# BeagleQ-v03.net
KiCad netlist of a schematic drawn in EAGLE
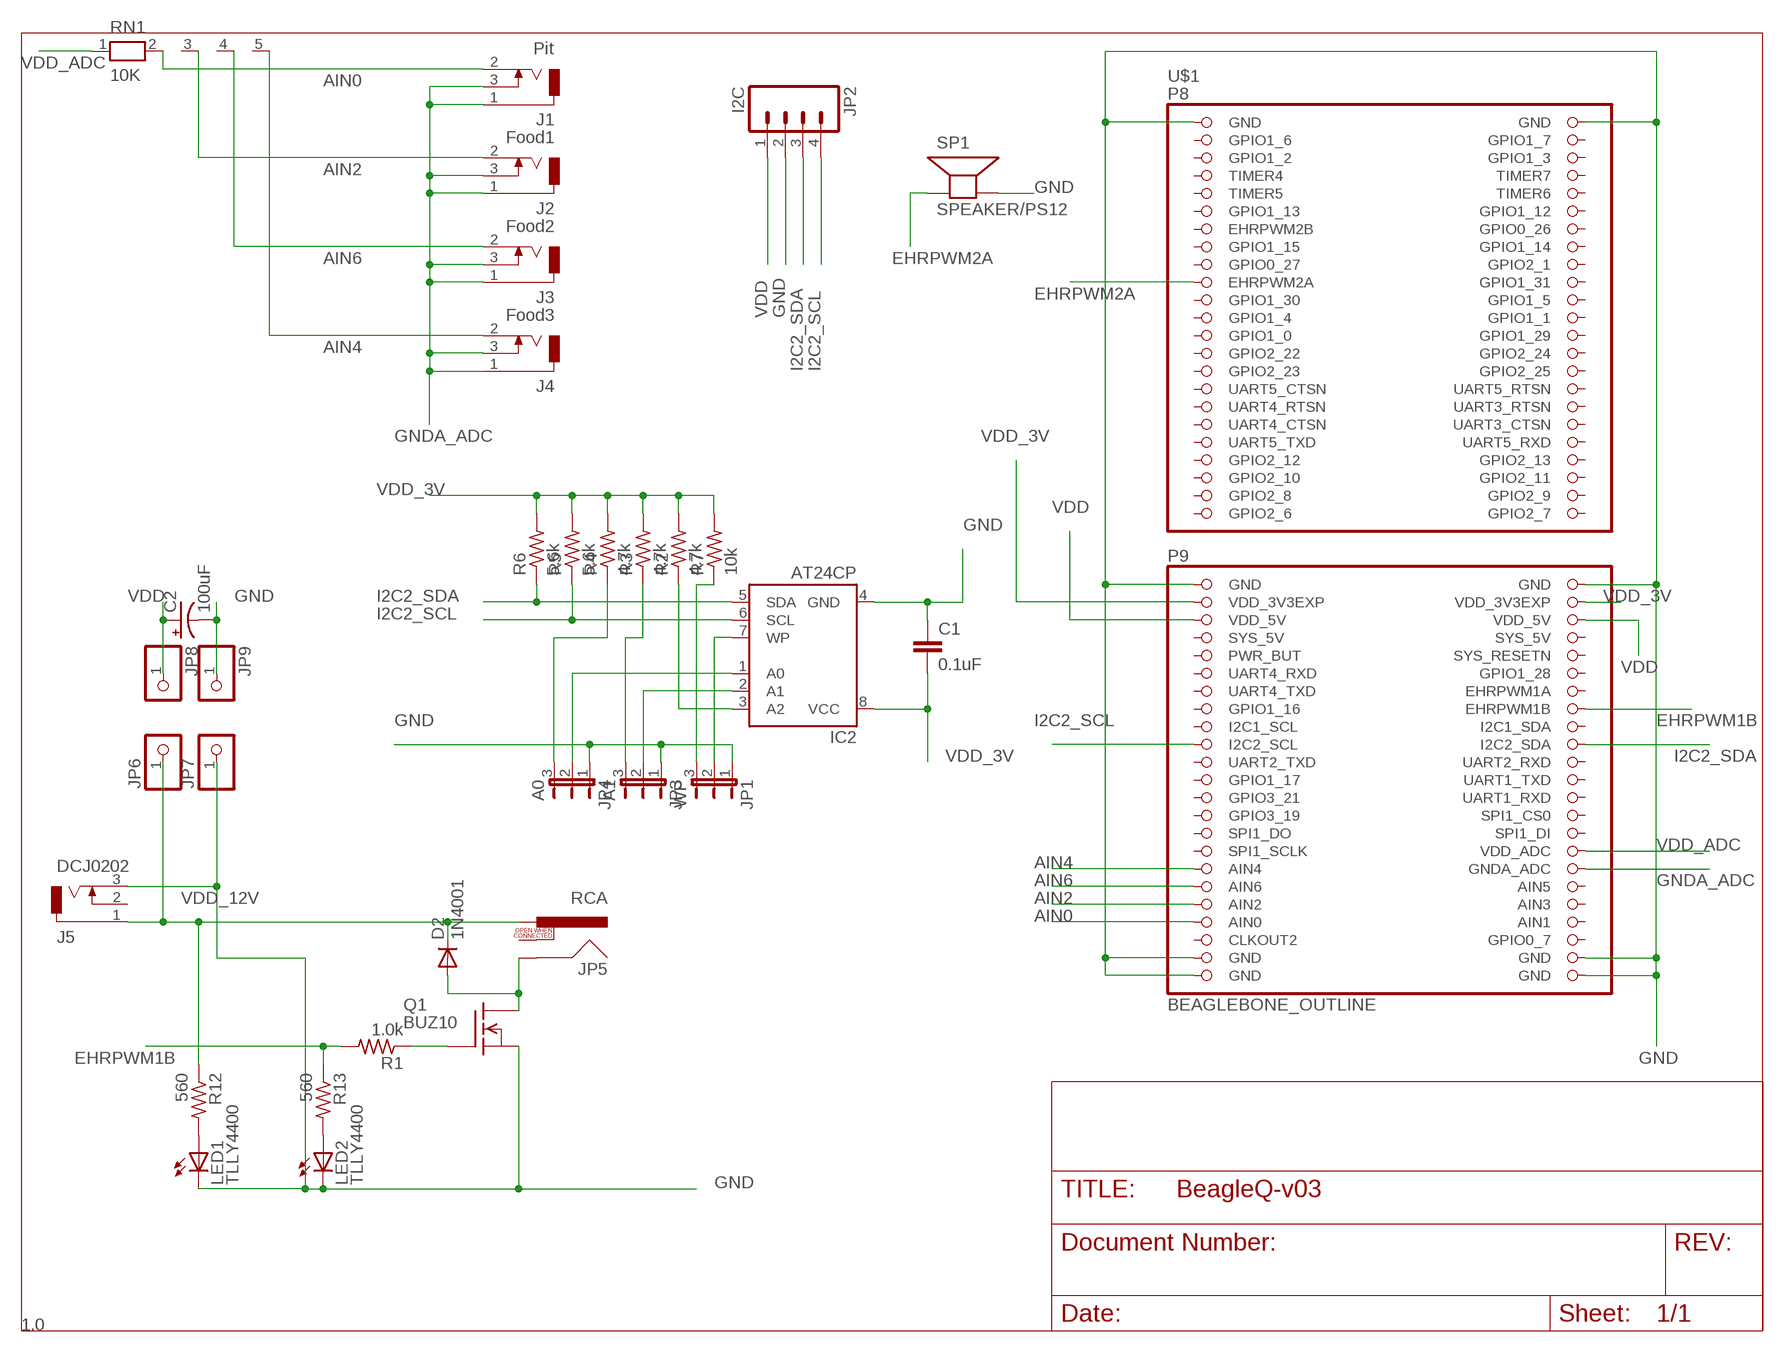
[diagram p0: schematic, sheet 1]

(export (version "E")
  (design (tool "Eeschema 10.0.6"))
  (components
    (comp (ref "C1")
      (value "0.1uF")
      (footprint "eagle-import:C2.5-2")
      (libsource (lib "eagle-import") (part "C2.5/2"))
    )
    (comp (ref "C2")
      (value "100uF")
      (footprint "eagle-import:E2,5-6E")
      (libsource (lib "eagle-import") (part "CPOL-USE2,5-6E"))
    )
    (comp (ref "D2")
      (value "1N4001")
      (footprint "eagle-import:DO41-10")
      (libsource (lib "eagle-import") (part "1N4004"))
    )
    (comp (ref "IC2")
      (value "AT24CP")
      (footprint "eagle-import:DIL08")
      (fields (field (name "MPN") "AT24C1024BW-SH-B"))
      (libsource (lib "eagle-import") (part "AT24CP"))
    )
    (comp (ref "J1")
      (value "Pit")
      (footprint "eagle-import:DCJ0202")
      (libsource (lib "eagle-import") (part "houseofbeck_DCJ0202"))
    )
    (comp (ref "J2")
      (value "Food1")
      (footprint "eagle-import:DCJ0202")
      (libsource (lib "eagle-import") (part "houseofbeck_DCJ0202"))
    )
    (comp (ref "J3")
      (value "Food2")
      (footprint "eagle-import:DCJ0202")
      (libsource (lib "eagle-import") (part "houseofbeck_DCJ0202"))
    )
    (comp (ref "J4")
      (value "Food3")
      (footprint "eagle-import:DCJ0202")
      (libsource (lib "eagle-import") (part "houseofbeck_DCJ0202"))
    )
    (comp (ref "J5")
      (value "DCJ0202")
      (footprint "eagle-import:DCJ0202")
      (libsource (lib "eagle-import") (part "DCJ0202"))
    )
    (comp (ref "JP1")
      (value "WP")
      (footprint "eagle-import:JP2")
      (libsource (lib "eagle-import") (part "JP2E"))
    )
    (comp (ref "JP2")
      (value "I2C")
      (footprint "eagle-import:1X04")
      (libsource (lib "eagle-import") (part "M04PTH"))
    )
    (comp (ref "JP3")
      (value "A1")
      (footprint "eagle-import:JP2")
      (libsource (lib "eagle-import") (part "JP2E"))
    )
    (comp (ref "JP4")
      (value "A0")
      (footprint "eagle-import:JP2")
      (libsource (lib "eagle-import") (part "JP2E"))
    )
    (comp (ref "JP5")
      (value "RCA")
      (footprint "eagle-import:RCA")
      (libsource (lib "eagle-import") (part "RCA"))
    )
    (comp (ref "JP6")
      (value "PINHD-1X1")
      (footprint "eagle-import:1X01")
      (libsource (lib "eagle-import") (part "PINHD-1X1"))
    )
    (comp (ref "JP7")
      (value "PINHD-1X1")
      (footprint "eagle-import:1X01")
      (libsource (lib "eagle-import") (part "PINHD-1X1"))
    )
    (comp (ref "JP8")
      (value "PINHD-1X1")
      (footprint "eagle-import:1X01")
      (libsource (lib "eagle-import") (part "PINHD-1X1"))
    )
    (comp (ref "JP9")
      (value "PINHD-1X1")
      (footprint "eagle-import:1X01")
      (libsource (lib "eagle-import") (part "PINHD-1X1"))
    )
    (comp (ref "LED1")
      (value "TLLY4400")
      (footprint "eagle-import:LED3MM")
      (fields (field (name "MF") "VISHAY SEMICONDUCTOR"))
      (libsource (lib "eagle-import") (part "TLLY4400"))
    )
    (comp (ref "LED2")
      (value "TLLY4400")
      (footprint "eagle-import:LED3MM")
      (fields (field (name "MF") "VISHAY SEMICONDUCTOR"))
      (libsource (lib "eagle-import") (part "TLLY4400"))
    )
    (comp (ref "Q1")
      (value "BUZ10")
      (footprint "eagle-import:TO220")
      (libsource (lib "eagle-import") (part "BUZ10"))
    )
    (comp (ref "R1")
      (value "1.0k")
      (footprint "eagle-import:0207_10")
      (libsource (lib "eagle-import") (part "R-US_0207/10"))
    )
    (comp (ref "R2")
      (value "4.7k")
      (footprint "eagle-import:0207_10")
      (libsource (lib "eagle-import") (part "R-US_0207/10"))
    )
    (comp (ref "R3")
      (value "4.7k")
      (footprint "eagle-import:0207_10")
      (libsource (lib "eagle-import") (part "R-US_0207/10"))
    )
    (comp (ref "R4")
      (value "4.7k")
      (footprint "eagle-import:0207_10")
      (libsource (lib "eagle-import") (part "R-US_0207/10"))
    )
    (comp (ref "R5")
      (value "5.6k")
      (footprint "eagle-import:0207_10")
      (libsource (lib "eagle-import") (part "R-US_0207/10"))
    )
    (comp (ref "R6")
      (value "5.6k")
      (footprint "eagle-import:0207_10")
      (libsource (lib "eagle-import") (part "R-US_0207/10"))
    )
    (comp (ref "R7")
      (value "10k")
      (footprint "eagle-import:0207_10")
      (libsource (lib "eagle-import") (part "R-US_0207/10"))
    )
    (comp (ref "R12")
      (value "560")
      (footprint "eagle-import:0207_10")
      (libsource (lib "eagle-import") (part "R-US_0207/10"))
    )
    (comp (ref "R13")
      (value "560")
      (footprint "eagle-import:0207_10")
      (libsource (lib "eagle-import") (part "R-US_0207/10"))
    )
    (comp (ref "RN1")
      (value "10K")
      (footprint "eagle-import:RN-5")
      (libsource (lib "eagle-import") (part "RN04"))
    )
    (comp (ref "SP1")
      (value "SPEAKER/PS12")
      (footprint "eagle-import:PS12")
      (libsource (lib "eagle-import") (part "SPEAKER/PS12"))
    )
    (comp (ref "U$1")
      (value "BEAGLEBONE_OUTLINE")
      (footprint "eagle-import:BEAGLEBONE_SHIELD")
      (libsource (lib "eagle-import") (part "BEAGLEBONE_OUTLINE"))
    )
  )
  (nets
    (net (code "1") (name "/AIN0") (class "Default")
      (node (ref "J1") (pin "2") (pinfunction "2_2") (pintype "passive"))
      (node (ref "RN1") (pin "2") (pinfunction "2_2") (pintype "passive"))
      (node (ref "U$1") (pin "85") (pinfunction "AIN0_85") (pintype "power_in"))
    )
    (net (code "2") (name "/AIN2") (class "Default")
      (node (ref "J2") (pin "2") (pinfunction "2_2") (pintype "passive"))
      (node (ref "RN1") (pin "3") (pinfunction "3_3") (pintype "passive"))
      (node (ref "U$1") (pin "83") (pinfunction "AIN2_83") (pintype "passive"))
    )
    (net (code "3") (name "/AIN4") (class "Default")
      (node (ref "J4") (pin "2") (pinfunction "2_2") (pintype "passive"))
      (node (ref "RN1") (pin "5") (pinfunction "5_5") (pintype "passive"))
      (node (ref "U$1") (pin "79") (pinfunction "AIN4_79") (pintype "passive"))
    )
    (net (code "4") (name "/AIN6") (class "Default")
      (node (ref "J3") (pin "2") (pinfunction "2_2") (pintype "passive"))
      (node (ref "RN1") (pin "4") (pinfunction "4_4") (pintype "passive"))
      (node (ref "U$1") (pin "81") (pinfunction "AIN6_81") (pintype "passive"))
    )
    (net (code "5") (name "/EHRPWM1B") (class "Default")
      (node (ref "R1") (pin "2") (pinfunction "2_2") (pintype "passive"))
      (node (ref "R13") (pin "1") (pinfunction "1_1") (pintype "passive"))
      (node (ref "U$1") (pin "62") (pinfunction "EHRPWM1B_62") (pintype "passive"))
    )
    (net (code "6") (name "/EHRPWM2A") (class "Default")
      (node (ref "SP1") (pin "P$1") (pinfunction "+_P$1") (pintype "passive"))
      (node (ref "U$1") (pin "19") (pinfunction "EHRPWM2A_19") (pintype "passive"))
    )
    (net (code "7") (name "/GND") (class "Default")
      (node (ref "C1") (pin "1") (pinfunction "1_1") (pintype "passive"))
      (node (ref "C2") (pin "-") (pinfunction "-_-") (pintype "passive"))
      (node (ref "IC2") (pin "4") (pinfunction "GND_4") (pintype "power_in"))
      (node (ref "J5") (pin "3") (pinfunction "3_3") (pintype "passive"))
      (node (ref "JP1") (pin "1") (pinfunction "1_1") (pintype "passive"))
      (node (ref "JP2") (pin "2") (pinfunction "2_2") (pintype "passive"))
      (node (ref "JP3") (pin "1") (pinfunction "1_1") (pintype "passive"))
      (node (ref "JP4") (pin "1") (pinfunction "1_1") (pintype "passive"))
      (node (ref "JP7") (pin "1") (pinfunction "1_1") (pintype "passive"))
      (node (ref "JP9") (pin "1") (pinfunction "1_1") (pintype "passive"))
      (node (ref "LED1") (pin "K") (pinfunction "C_K") (pintype "passive"))
      (node (ref "LED2") (pin "K") (pinfunction "C_K") (pintype "passive"))
      (node (ref "Q1") (pin "3") (pinfunction "S_3") (pintype "passive"))
      (node (ref "SP1") (pin "P$2") (pinfunction "-_P$2") (pintype "passive"))
      (node (ref "U$1") (pin "1") (pinfunction "GND_1") (pintype "power_in"))
      (node (ref "U$1") (pin "2") (pinfunction "GND_2") (pintype "power_in"))
      (node (ref "U$1") (pin "47") (pinfunction "GND_47") (pintype "power_in"))
      (node (ref "U$1") (pin "48") (pinfunction "GND_48") (pintype "power_in"))
      (node (ref "U$1") (pin "89") (pinfunction "GND_89") (pintype "power_in"))
      (node (ref "U$1") (pin "90") (pinfunction "GND_90") (pintype "power_in"))
      (node (ref "U$1") (pin "91") (pinfunction "GND_91") (pintype "power_in"))
      (node (ref "U$1") (pin "92") (pinfunction "GND_92") (pintype "power_in"))
    )
    (net (code "8") (name "/GNDA_ADC") (class "Default")
      (node (ref "J1") (pin "1") (pinfunction "1_1") (pintype "passive"))
      (node (ref "J1") (pin "3") (pinfunction "3_3") (pintype "passive"))
      (node (ref "J2") (pin "1") (pinfunction "1_1") (pintype "passive"))
      (node (ref "J2") (pin "3") (pinfunction "3_3") (pintype "passive"))
      (node (ref "J3") (pin "1") (pinfunction "1_1") (pintype "passive"))
      (node (ref "J3") (pin "3") (pinfunction "3_3") (pintype "passive"))
      (node (ref "J4") (pin "1") (pinfunction "1_1") (pintype "passive"))
      (node (ref "J4") (pin "3") (pinfunction "3_3") (pintype "passive"))
      (node (ref "U$1") (pin "80") (pinfunction "GNDA_ADC_80") (pintype "passive"))
    )
    (net (code "9") (name "/I2C2_SCL") (class "Default")
      (node (ref "IC2") (pin "6") (pinfunction "SCL_6") (pintype "bidirectional"))
      (node (ref "JP2") (pin "4") (pinfunction "4_4") (pintype "passive"))
      (node (ref "R5") (pin "1") (pinfunction "1_1") (pintype "passive"))
      (node (ref "U$1") (pin "65") (pinfunction "I2C2_SCL_65") (pintype "passive"))
    )
    (net (code "10") (name "/I2C2_SDA") (class "Default")
      (node (ref "IC2") (pin "5") (pinfunction "SDA_5") (pintype "bidirectional"))
      (node (ref "JP2") (pin "3") (pinfunction "3_3") (pintype "passive"))
      (node (ref "R6") (pin "1") (pinfunction "1_1") (pintype "passive"))
      (node (ref "U$1") (pin "66") (pinfunction "I2C2_SDA_66") (pintype "passive"))
    )
    (net (code "11") (name "/SYS_5V") (class "Default")
      (node (ref "U$1") (pin "53") (pinfunction "SYS_5V_53") (pintype "power_in"))
    )
    (net (code "12") (name "/VDD") (class "Default")
      (node (ref "C2") (pin "+") (pinfunction "+_+") (pintype "passive"))
      (node (ref "JP2") (pin "1") (pinfunction "1_1") (pintype "passive"))
      (node (ref "JP8") (pin "1") (pinfunction "1_1") (pintype "passive"))
      (node (ref "U$1") (pin "51") (pinfunction "VDD_5V_51") (pintype "power_in"))
      (node (ref "U$1") (pin "52") (pinfunction "VDD_5V_52") (pintype "power_in"))
    )
    (net (code "13") (name "/VDD_3V") (class "Default")
      (node (ref "C1") (pin "2") (pinfunction "2_2") (pintype "passive"))
      (node (ref "IC2") (pin "8") (pinfunction "VCC_8") (pintype "power_in"))
      (node (ref "R2") (pin "2") (pinfunction "2_2") (pintype "passive"))
      (node (ref "R3") (pin "2") (pinfunction "2_2") (pintype "passive"))
      (node (ref "R4") (pin "2") (pinfunction "2_2") (pintype "passive"))
      (node (ref "R5") (pin "2") (pinfunction "2_2") (pintype "passive"))
      (node (ref "R6") (pin "2") (pinfunction "2_2") (pintype "passive"))
      (node (ref "R7") (pin "2") (pinfunction "2_2") (pintype "passive"))
      (node (ref "U$1") (pin "49") (pinfunction "VDD_3V3EXP_49") (pintype "power_in"))
      (node (ref "U$1") (pin "50") (pinfunction "VDD_3V3EXP_50") (pintype "power_in"))
    )
    (net (code "14") (name "/VDD_12V") (class "Default")
      (node (ref "D2") (pin "C") (pinfunction "C_C") (pintype "passive"))
      (node (ref "J5") (pin "1") (pinfunction "1_1") (pintype "passive"))
      (node (ref "JP5") (pin "PIN") (pinfunction "PIN_PIN") (pintype "bidirectional"))
      (node (ref "JP6") (pin "1") (pinfunction "1_1") (pintype "passive"))
      (node (ref "R12") (pin "1") (pinfunction "1_1") (pintype "passive"))
    )
    (net (code "15") (name "/VDD_ADC") (class "Default")
      (node (ref "RN1") (pin "1") (pinfunction "1_1") (pintype "passive"))
      (node (ref "U$1") (pin "78") (pinfunction "VDD_ADC_78") (pintype "passive"))
    )
    (net (code "16") (name "Net-(IC2-A0)") (class "Default")
      (node (ref "IC2") (pin "1") (pinfunction "A0_1") (pintype "input"))
      (node (ref "JP4") (pin "2") (pinfunction "2_2") (pintype "passive"))
    )
    (net (code "17") (name "Net-(IC2-A1)") (class "Default")
      (node (ref "IC2") (pin "2") (pinfunction "A1_2") (pintype "input"))
      (node (ref "JP3") (pin "2") (pinfunction "2_2") (pintype "passive"))
    )
    (net (code "18") (name "Net-(IC2-A2)") (class "Default")
      (node (ref "IC2") (pin "3") (pinfunction "A2_3") (pintype "input"))
      (node (ref "R2") (pin "1") (pinfunction "1_1") (pintype "passive"))
    )
    (net (code "19") (name "Net-(IC2-WP)") (class "Default")
      (node (ref "IC2") (pin "7") (pinfunction "WP_7") (pintype "input"))
      (node (ref "JP1") (pin "2") (pinfunction "2_2") (pintype "passive"))
    )
    (net (code "20") (name "Net-(JP1-Pad3)") (class "Default")
      (node (ref "JP1") (pin "3") (pinfunction "3_3") (pintype "passive"))
      (node (ref "R7") (pin "1") (pinfunction "1_1") (pintype "passive"))
    )
    (net (code "21") (name "Net-(JP3-Pad3)") (class "Default")
      (node (ref "JP3") (pin "3") (pinfunction "3_3") (pintype "passive"))
      (node (ref "R3") (pin "1") (pinfunction "1_1") (pintype "passive"))
    )
    (net (code "22") (name "Net-(JP4-Pad3)") (class "Default")
      (node (ref "JP4") (pin "3") (pinfunction "3_3") (pintype "passive"))
      (node (ref "R4") (pin "1") (pinfunction "1_1") (pintype "passive"))
    )
    (net (code "23") (name "Net-(LED1-PadA)") (class "Default")
      (node (ref "LED1") (pin "A") (pinfunction "A_A") (pintype "passive"))
      (node (ref "R12") (pin "2") (pinfunction "2_2") (pintype "passive"))
    )
    (net (code "24") (name "Net-(LED2-PadA)") (class "Default")
      (node (ref "LED2") (pin "A") (pinfunction "A_A") (pintype "passive"))
      (node (ref "R13") (pin "2") (pinfunction "2_2") (pintype "passive"))
    )
    (net (code "25") (name "Net-(Q1-D)") (class "Default")
      (node (ref "D2") (pin "A") (pinfunction "A_A") (pintype "passive"))
      (node (ref "JP5") (pin "SHELL") (pinfunction "SHELL_SHELL") (pintype "bidirectional"))
      (node (ref "Q1") (pin "2") (pinfunction "D_2") (pintype "passive"))
    )
    (net (code "26") (name "Net-(Q1-G)") (class "Default")
      (node (ref "Q1") (pin "1") (pinfunction "G_1") (pintype "passive"))
      (node (ref "R1") (pin "1") (pinfunction "1_1") (pintype "passive"))
    )
    (net (code "27") (name "unconnected-(J5-Pad2)") (class "Default")
      (node (ref "J5") (pin "2") (pinfunction "2_2") (pintype "passive"))
    )
    (net (code "28") (name "unconnected-(JP5-PadSWITCH)") (class "Default")
      (node (ref "JP5") (pin "SWITCH") (pinfunction "SWITCH_SWITCH") (pintype "bidirectional"))
    )
    (net (code "29") (name "unconnected-(U$1-AIN1-Pad86)") (class "Default")
      (node (ref "U$1") (pin "86") (pinfunction "AIN1_86") (pintype "passive"))
    )
    (net (code "30") (name "unconnected-(U$1-AIN3-Pad84)") (class "Default")
      (node (ref "U$1") (pin "84") (pinfunction "AIN3_84") (pintype "passive"))
    )
    (net (code "31") (name "unconnected-(U$1-AIN5-Pad82)") (class "Default")
      (node (ref "U$1") (pin "82") (pinfunction "AIN5_82") (pintype "passive"))
    )
    (net (code "32") (name "unconnected-(U$1-CLKOUT2-Pad87)") (class "Default")
      (node (ref "U$1") (pin "87") (pinfunction "CLKOUT2_87") (pintype "input"))
    )
    (net (code "33") (name "unconnected-(U$1-EHRPWM1A-Pad60)") (class "Default")
      (node (ref "U$1") (pin "60") (pinfunction "EHRPWM1A_60") (pintype "passive"))
    )
    (net (code "34") (name "unconnected-(U$1-EHRPWM2B-Pad13)") (class "Default")
      (node (ref "U$1") (pin "13") (pinfunction "EHRPWM2B_13") (pintype "passive"))
    )
    (net (code "35") (name "unconnected-(U$1-GPIO0_7-Pad88)") (class "Default")
      (node (ref "U$1") (pin "88") (pinfunction "GPIO0_7_88") (pintype "passive"))
    )
    (net (code "36") (name "unconnected-(U$1-GPIO0_26-Pad14)") (class "Default")
      (node (ref "U$1") (pin "14") (pinfunction "GPIO0_26_14") (pintype "passive"))
    )
    (net (code "37") (name "unconnected-(U$1-GPIO0_27-Pad17)") (class "Default")
      (node (ref "U$1") (pin "17") (pinfunction "GPIO0_27_17") (pintype "passive"))
    )
    (net (code "38") (name "unconnected-(U$1-GPIO1_0-Pad25)") (class "Default")
      (node (ref "U$1") (pin "25") (pinfunction "GPIO1_0_25") (pintype "passive"))
    )
    (net (code "39") (name "unconnected-(U$1-GPIO1_1-Pad24)") (class "Default")
      (node (ref "U$1") (pin "24") (pinfunction "GPIO1_1_24") (pintype "passive"))
    )
    (net (code "40") (name "unconnected-(U$1-GPIO1_2-Pad5)") (class "Default")
      (node (ref "U$1") (pin "5") (pinfunction "GPIO1_2_5") (pintype "passive"))
    )
    (net (code "41") (name "unconnected-(U$1-GPIO1_3-Pad6)") (class "Default")
      (node (ref "U$1") (pin "6") (pinfunction "GPIO1_3_6") (pintype "passive"))
    )
    (net (code "42") (name "unconnected-(U$1-GPIO1_4-Pad23)") (class "Default")
      (node (ref "U$1") (pin "23") (pinfunction "GPIO1_4_23") (pintype "passive"))
    )
    (net (code "43") (name "unconnected-(U$1-GPIO1_5-Pad22)") (class "Default")
      (node (ref "U$1") (pin "22") (pinfunction "GPIO1_5_22") (pintype "passive"))
    )
    (net (code "44") (name "unconnected-(U$1-GPIO1_6-Pad3)") (class "Default")
      (node (ref "U$1") (pin "3") (pinfunction "GPIO1_6_3") (pintype "passive"))
    )
    (net (code "45") (name "unconnected-(U$1-GPIO1_7-Pad4)") (class "Default")
      (node (ref "U$1") (pin "4") (pinfunction "GPIO1_7_4") (pintype "passive"))
    )
    (net (code "46") (name "unconnected-(U$1-GPIO1_12-Pad12)") (class "Default")
      (node (ref "U$1") (pin "12") (pinfunction "GPIO1_12_12") (pintype "passive"))
    )
    (net (code "47") (name "unconnected-(U$1-GPIO1_13-Pad11)") (class "Default")
      (node (ref "U$1") (pin "11") (pinfunction "GPIO1_13_11") (pintype "passive"))
    )
    (net (code "48") (name "unconnected-(U$1-GPIO1_14-Pad16)") (class "Default")
      (node (ref "U$1") (pin "16") (pinfunction "GPIO1_14_16") (pintype "passive"))
    )
    (net (code "49") (name "unconnected-(U$1-GPIO1_15-Pad15)") (class "Default")
      (node (ref "U$1") (pin "15") (pinfunction "GPIO1_15_15") (pintype "passive"))
    )
    (net (code "50") (name "unconnected-(U$1-GPIO1_16-Pad61)") (class "Default")
      (node (ref "U$1") (pin "61") (pinfunction "GPIO1_16_61") (pintype "passive"))
    )
    (net (code "51") (name "unconnected-(U$1-GPIO1_17-Pad69)") (class "Default")
      (node (ref "U$1") (pin "69") (pinfunction "GPIO1_17_69") (pintype "passive"))
    )
    (net (code "52") (name "unconnected-(U$1-GPIO1_28-Pad58)") (class "Default")
      (node (ref "U$1") (pin "58") (pinfunction "GPIO1_28_58") (pintype "passive"))
    )
    (net (code "53") (name "unconnected-(U$1-GPIO1_29-Pad26)") (class "Default")
      (node (ref "U$1") (pin "26") (pinfunction "GPIO1_29_26") (pintype "passive"))
    )
    (net (code "54") (name "unconnected-(U$1-GPIO1_30-Pad21)") (class "Default")
      (node (ref "U$1") (pin "21") (pinfunction "GPIO1_30_21") (pintype "passive"))
    )
    (net (code "55") (name "unconnected-(U$1-GPIO1_31-Pad20)") (class "Default")
      (node (ref "U$1") (pin "20") (pinfunction "GPIO1_31_20") (pintype "passive"))
    )
    (net (code "56") (name "unconnected-(U$1-GPIO2_1-Pad18)") (class "Default")
      (node (ref "U$1") (pin "18") (pinfunction "GPIO2_1_18") (pintype "passive"))
    )
    (net (code "57") (name "unconnected-(U$1-GPIO2_6-Pad45)") (class "Default")
      (node (ref "U$1") (pin "45") (pinfunction "GPIO2_6_45") (pintype "passive"))
    )
    (net (code "58") (name "unconnected-(U$1-GPIO2_7-Pad46)") (class "Default")
      (node (ref "U$1") (pin "46") (pinfunction "GPIO2_7_46") (pintype "passive"))
    )
    (net (code "59") (name "unconnected-(U$1-GPIO2_8-Pad43)") (class "Default")
      (node (ref "U$1") (pin "43") (pinfunction "GPIO2_8_43") (pintype "passive"))
    )
    (net (code "60") (name "unconnected-(U$1-GPIO2_9-Pad44)") (class "Default")
      (node (ref "U$1") (pin "44") (pinfunction "GPIO2_9_44") (pintype "passive"))
    )
    (net (code "61") (name "unconnected-(U$1-GPIO2_10-Pad41)") (class "Default")
      (node (ref "U$1") (pin "41") (pinfunction "GPIO2_10_41") (pintype "passive"))
    )
    (net (code "62") (name "unconnected-(U$1-GPIO2_11-Pad42)") (class "Default")
      (node (ref "U$1") (pin "42") (pinfunction "GPIO2_11_42") (pintype "passive"))
    )
    (net (code "63") (name "unconnected-(U$1-GPIO2_12-Pad39)") (class "Default")
      (node (ref "U$1") (pin "39") (pinfunction "GPIO2_12_39") (pintype "passive"))
    )
    (net (code "64") (name "unconnected-(U$1-GPIO2_13-Pad40)") (class "Default")
      (node (ref "U$1") (pin "40") (pinfunction "GPIO2_13_40") (pintype "passive"))
    )
    (net (code "65") (name "unconnected-(U$1-GPIO2_22-Pad27)") (class "Default")
      (node (ref "U$1") (pin "27") (pinfunction "GPIO2_22_27") (pintype "passive"))
    )
    (net (code "66") (name "unconnected-(U$1-GPIO2_23-Pad29)") (class "Default")
      (node (ref "U$1") (pin "29") (pinfunction "GPIO2_23_29") (pintype "passive"))
    )
    (net (code "67") (name "unconnected-(U$1-GPIO2_24-Pad28)") (class "Default")
      (node (ref "U$1") (pin "28") (pinfunction "GPIO2_24_28") (pintype "passive"))
    )
    (net (code "68") (name "unconnected-(U$1-GPIO2_25-Pad30)") (class "Default")
      (node (ref "U$1") (pin "30") (pinfunction "GPIO2_25_30") (pintype "passive"))
    )
    (net (code "69") (name "unconnected-(U$1-GPIO3_19-Pad73)") (class "Default")
      (node (ref "U$1") (pin "73") (pinfunction "GPIO3_19_73") (pintype "passive"))
    )
    (net (code "70") (name "unconnected-(U$1-GPIO3_21-Pad71)") (class "Default")
      (node (ref "U$1") (pin "71") (pinfunction "GPIO3_21_71") (pintype "passive"))
    )
    (net (code "71") (name "unconnected-(U$1-I2C1_SCL-Pad63)") (class "Default")
      (node (ref "U$1") (pin "63") (pinfunction "I2C1_SCL_63") (pintype "passive"))
    )
    (net (code "72") (name "unconnected-(U$1-I2C1_SDA-Pad64)") (class "Default")
      (node (ref "U$1") (pin "64") (pinfunction "I2C1_SDA_64") (pintype "passive"))
    )
    (net (code "73") (name "unconnected-(U$1-PWR_BUT-Pad55)") (class "Default")
      (node (ref "U$1") (pin "55") (pinfunction "PWR_BUT_55") (pintype "passive"))
    )
    (net (code "74") (name "unconnected-(U$1-SPI1_CS0-Pad74)") (class "Default")
      (node (ref "U$1") (pin "74") (pinfunction "SPI1_CS0_74") (pintype "passive"))
    )
    (net (code "75") (name "unconnected-(U$1-SPI1_DI-Pad76)") (class "Default")
      (node (ref "U$1") (pin "76") (pinfunction "SPI1_DI_76") (pintype "passive"))
    )
    (net (code "76") (name "unconnected-(U$1-SPI1_DO-Pad75)") (class "Default")
      (node (ref "U$1") (pin "75") (pinfunction "SPI1_DO_75") (pintype "passive"))
    )
    (net (code "77") (name "unconnected-(U$1-SPI1_SCLK-Pad77)") (class "Default")
      (node (ref "U$1") (pin "77") (pinfunction "SPI1_SCLK_77") (pintype "passive"))
    )
    (net (code "78") (name "unconnected-(U$1-SYS_5V-Pad54)") (class "Default")
      (node (ref "U$1") (pin "54") (pinfunction "SYS_5V_54") (pintype "passive"))
    )
    (net (code "79") (name "unconnected-(U$1-SYS_RESETN-Pad56)") (class "Default")
      (node (ref "U$1") (pin "56") (pinfunction "SYS_RESETN_56") (pintype "passive"))
    )
    (net (code "80") (name "unconnected-(U$1-TIMER4-Pad7)") (class "Default")
      (node (ref "U$1") (pin "7") (pinfunction "TIMER4_7") (pintype "passive"))
    )
    (net (code "81") (name "unconnected-(U$1-TIMER5-Pad9)") (class "Default")
      (node (ref "U$1") (pin "9") (pinfunction "TIMER5_9") (pintype "passive"))
    )
    (net (code "82") (name "unconnected-(U$1-TIMER6-Pad10)") (class "Default")
      (node (ref "U$1") (pin "10") (pinfunction "TIMER6_10") (pintype "passive"))
    )
    (net (code "83") (name "unconnected-(U$1-TIMER7-Pad8)") (class "Default")
      (node (ref "U$1") (pin "8") (pinfunction "TIMER7_8") (pintype "passive"))
    )
    (net (code "84") (name "unconnected-(U$1-UART1_RXD-Pad72)") (class "Default")
      (node (ref "U$1") (pin "72") (pinfunction "UART1_RXD_72") (pintype "passive"))
    )
    (net (code "85") (name "unconnected-(U$1-UART1_TXD-Pad70)") (class "Default")
      (node (ref "U$1") (pin "70") (pinfunction "UART1_TXD_70") (pintype "passive"))
    )
    (net (code "86") (name "unconnected-(U$1-UART2_RXD-Pad68)") (class "Default")
      (node (ref "U$1") (pin "68") (pinfunction "UART2_RXD_68") (pintype "passive"))
    )
    (net (code "87") (name "unconnected-(U$1-UART2_TXD-Pad67)") (class "Default")
      (node (ref "U$1") (pin "67") (pinfunction "UART2_TXD_67") (pintype "passive"))
    )
    (net (code "88") (name "unconnected-(U$1-UART3_CTSN-Pad36)") (class "Default")
      (node (ref "U$1") (pin "36") (pinfunction "UART3_CTSN_36") (pintype "passive"))
    )
    (net (code "89") (name "unconnected-(U$1-UART3_RTSN-Pad34)") (class "Default")
      (node (ref "U$1") (pin "34") (pinfunction "UART3_RTSN_34") (pintype "passive"))
    )
    (net (code "90") (name "unconnected-(U$1-UART4_CTSN-Pad35)") (class "Default")
      (node (ref "U$1") (pin "35") (pinfunction "UART4_CTSN_35") (pintype "passive"))
    )
    (net (code "91") (name "unconnected-(U$1-UART4_RTSN-Pad33)") (class "Default")
      (node (ref "U$1") (pin "33") (pinfunction "UART4_RTSN_33") (pintype "passive"))
    )
    (net (code "92") (name "unconnected-(U$1-UART4_RXD-Pad57)") (class "Default")
      (node (ref "U$1") (pin "57") (pinfunction "UART4_RXD_57") (pintype "passive"))
    )
    (net (code "93") (name "unconnected-(U$1-UART4_TXD-Pad59)") (class "Default")
      (node (ref "U$1") (pin "59") (pinfunction "UART4_TXD_59") (pintype "passive"))
    )
    (net (code "94") (name "unconnected-(U$1-UART5_CTSN-Pad31)") (class "Default")
      (node (ref "U$1") (pin "31") (pinfunction "UART5_CTSN_31") (pintype "passive"))
    )
    (net (code "95") (name "unconnected-(U$1-UART5_RTSN-Pad32)") (class "Default")
      (node (ref "U$1") (pin "32") (pinfunction "UART5_RTSN_32") (pintype "passive"))
    )
    (net (code "96") (name "unconnected-(U$1-UART5_RXD-Pad38)") (class "Default")
      (node (ref "U$1") (pin "38") (pinfunction "UART5_RXD_38") (pintype "passive"))
    )
    (net (code "97") (name "unconnected-(U$1-UART5_TXD-Pad37)") (class "Default")
      (node (ref "U$1") (pin "37") (pinfunction "UART5_TXD_37") (pintype "passive"))
    )
  )
)
